# flashbutton.net
KiCad netlist of a schematic drawn in EAGLE
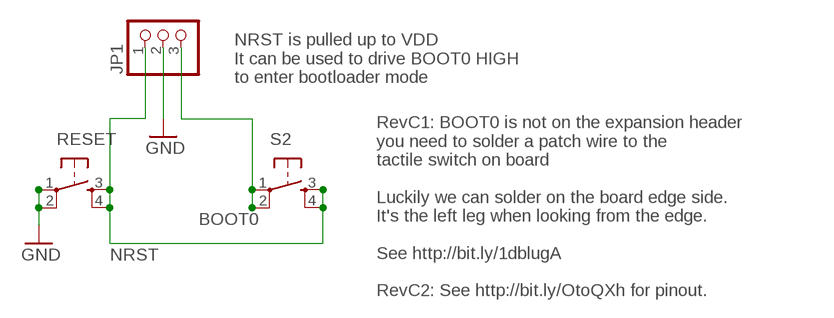
[diagram p0: schematic, sheet 1]

(export (version "E")
  (design (tool "Eeschema 10.0.6"))
  (components
    (comp (ref "JP1")
      (value "PINHD-1X3")
      (footprint "eagle-import:1X03")
      (libsource (lib "eagle-import") (part "PINHD-1X3"))
    )
    (comp (ref "RESET")
      (value "TAC_SWITCHSMD")
      (footprint "eagle-import:TACTILE_SWITCH_SMD")
      (libsource (lib "eagle-import") (part "TAC_SWITCHSMD"))
    )
    (comp (ref "S2")
      (value "TAC_SWITCHSMD")
      (footprint "eagle-import:TACTILE_SWITCH_SMD")
      (libsource (lib "eagle-import") (part "TAC_SWITCHSMD"))
    )
  )
  (nets
    (net (code "1") (name "/BOOT0") (class "Default")
      (node (ref "JP1") (pin "3") (pinfunction "3_3") (pintype "passive"))
      (node (ref "S2") (pin "1") (pinfunction "1_1") (pintype "passive"))
      (node (ref "S2") (pin "2") (pinfunction "2_2") (pintype "passive"))
    )
    (net (code "2") (name "/NRST") (class "Default")
      (node (ref "JP1") (pin "1") (pinfunction "1_1") (pintype "passive"))
      (node (ref "RESET") (pin "3") (pinfunction "3_3") (pintype "passive"))
      (node (ref "RESET") (pin "4") (pinfunction "4_4") (pintype "passive"))
      (node (ref "S2") (pin "3") (pinfunction "3_3") (pintype "passive"))
      (node (ref "S2") (pin "4") (pinfunction "4_4") (pintype "passive"))
    )
    (net (code "3") (name "GND") (class "Default")
      (node (ref "JP1") (pin "2") (pinfunction "2_2") (pintype "passive"))
      (node (ref "RESET") (pin "1") (pinfunction "1_1") (pintype "passive"))
      (node (ref "RESET") (pin "2") (pinfunction "2_2") (pintype "passive"))
    )
  )
)
